# mapleCUx_large_210.net
KiCad netlist of a schematic drawn in EAGLE
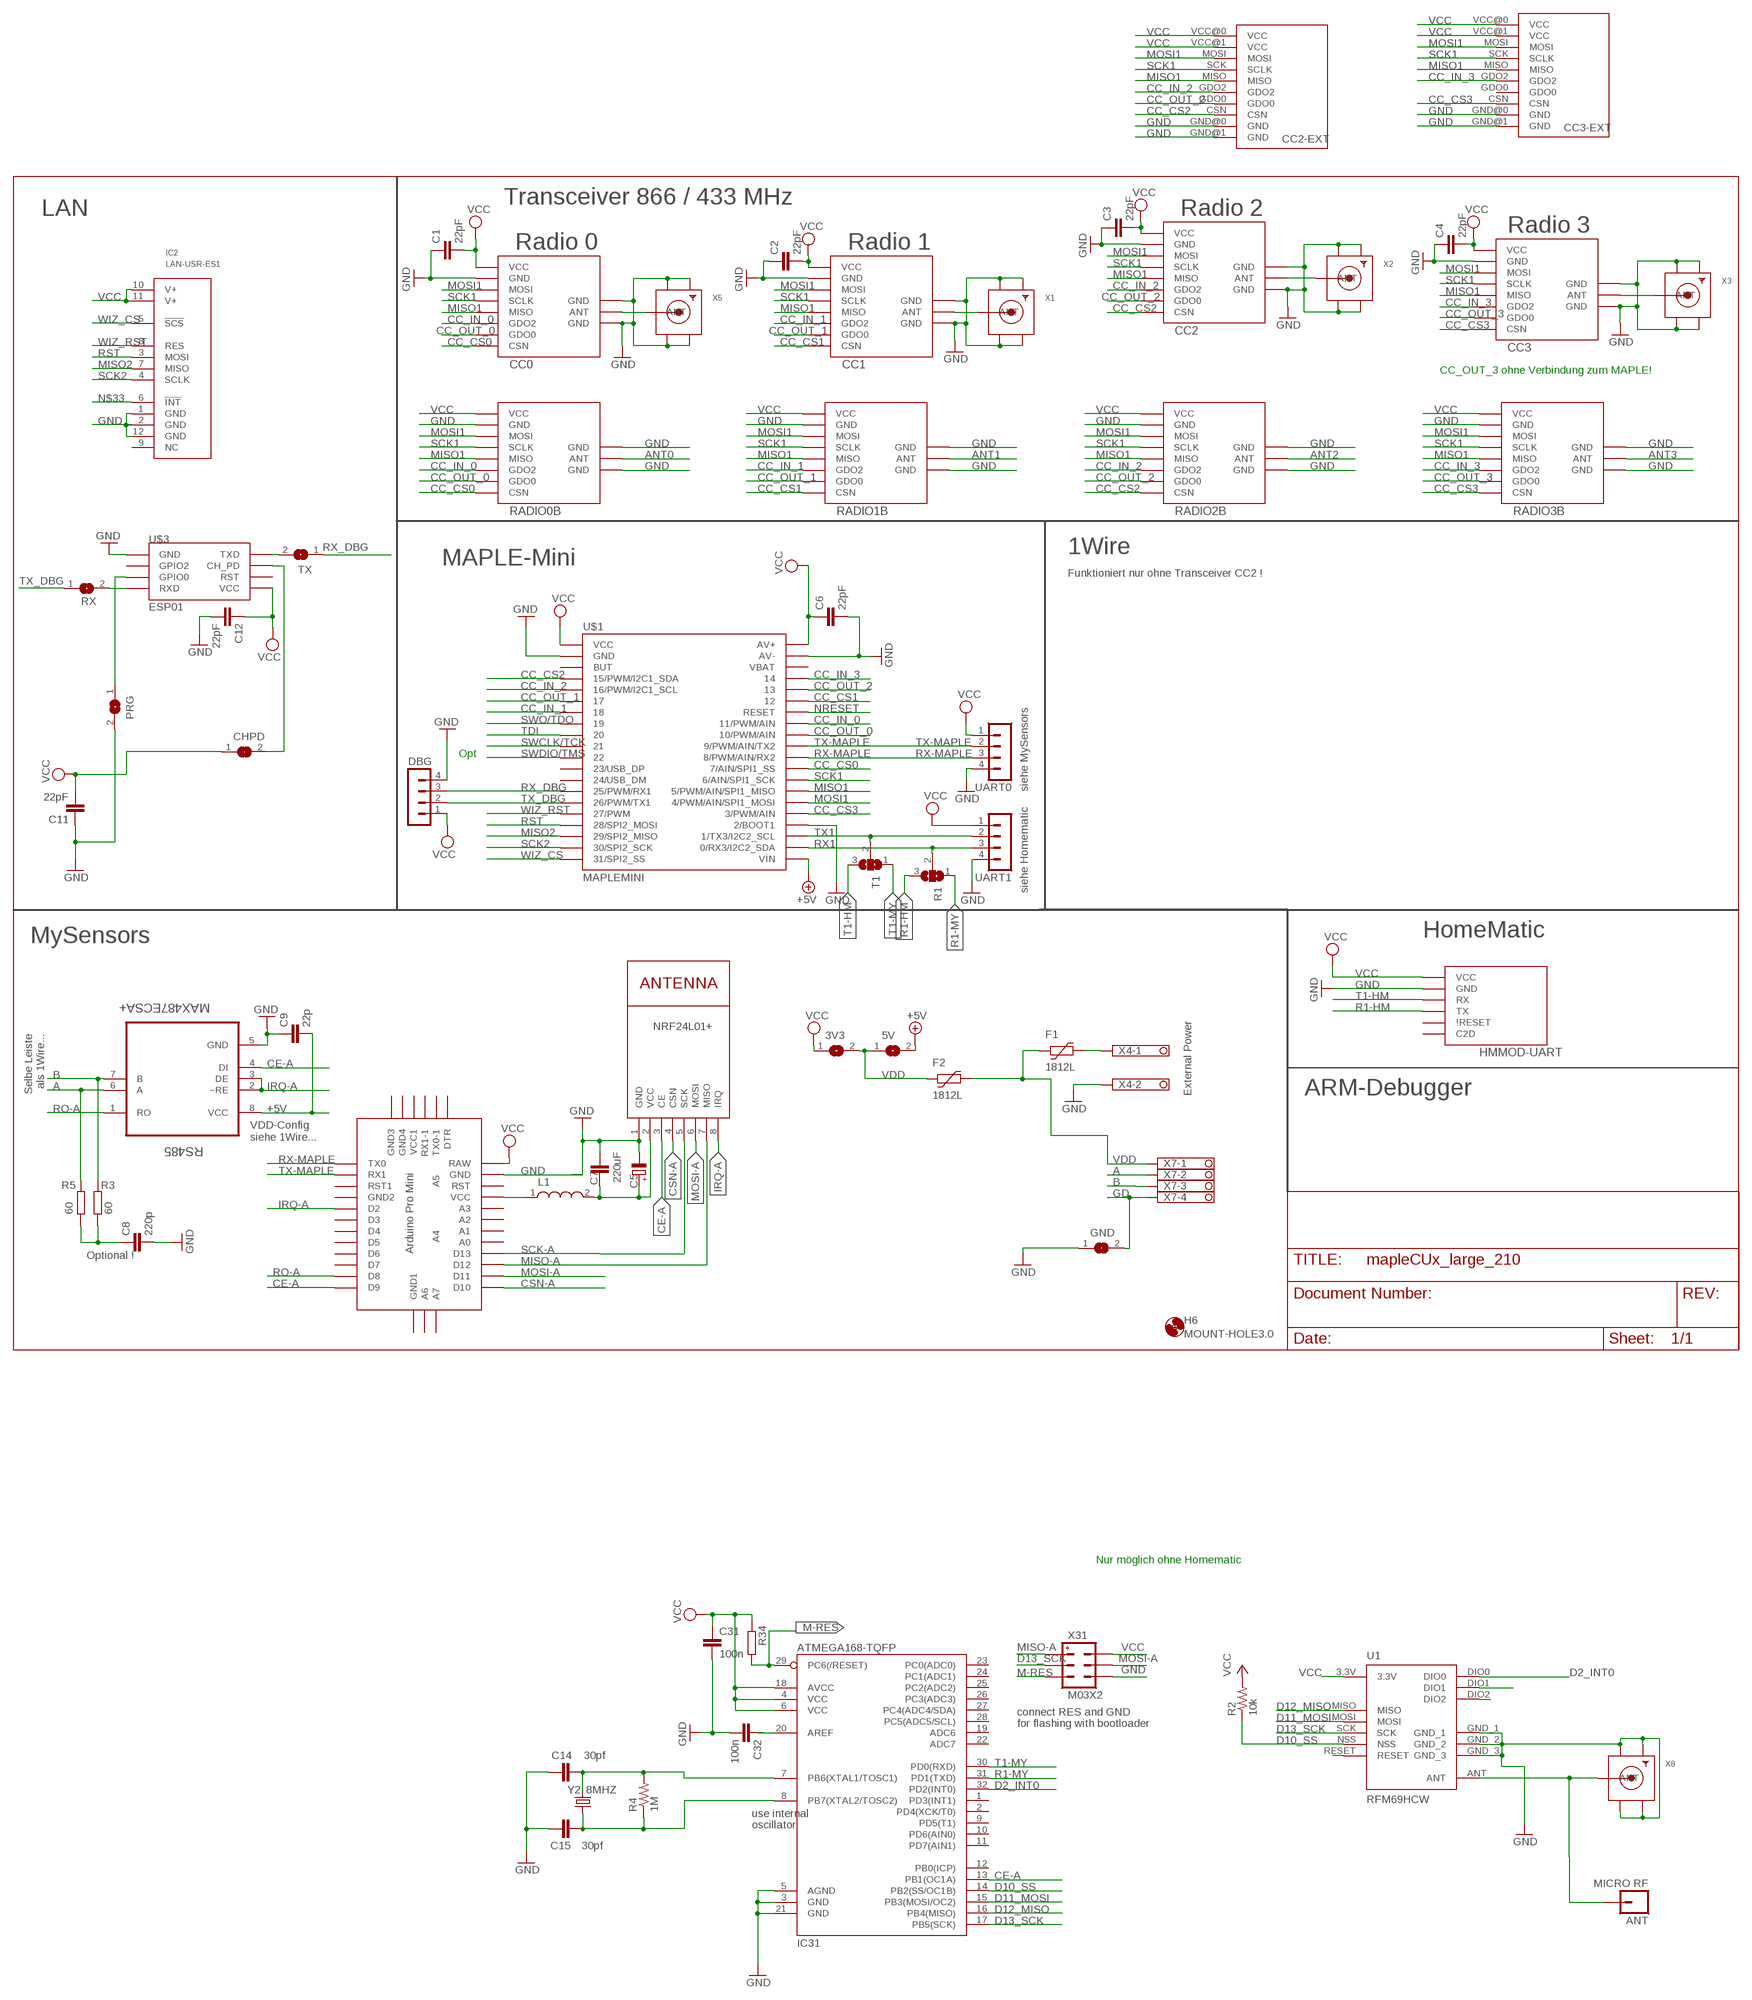
[diagram p0: schematic, sheet 1]

(export (version "E")
  (design (tool "Eeschema 10.0.6"))
  (components
    (comp (ref "3V3") (value "SJ") (footprint "eagle-import:SJ") (libsource (lib "eagle-import") (part "SJ")))
    (comp (ref "5V") (value "SJ") (footprint "eagle-import:SJ") (libsource (lib "eagle-import") (part "SJ")))
    (comp (ref "ANT")
      (value "MICRO RF")
      (footprint "eagle-import:1X01")
      (libsource (lib "eagle-import") (part "M01PTH"))
    )
    (comp (ref "C1")
      (value "22pF")
      (footprint "eagle-import:C0805")
      (libsource (lib "eagle-import") (part "C-EUC0805"))
    )
    (comp (ref "C2")
      (value "22pF")
      (footprint "eagle-import:C0805")
      (libsource (lib "eagle-import") (part "C-EUC0805"))
    )
    (comp (ref "C3")
      (value "22pF")
      (footprint "eagle-import:C0805")
      (libsource (lib "eagle-import") (part "C-EUC0805"))
    )
    (comp (ref "C4")
      (value "22pF")
      (footprint "eagle-import:C0805")
      (libsource (lib "eagle-import") (part "C-EUC0805"))
    )
    (comp (ref "C5")
      (value "220uF")
      (footprint "eagle-import:E5-8,5")
      (libsource (lib "eagle-import") (part "CPOL-EUE5-8.5"))
    )
    (comp (ref "C6")
      (value "22pF")
      (footprint "eagle-import:C0805")
      (libsource (lib "eagle-import") (part "C-EUC0805"))
    )
    (comp (ref "C7")
      (value "C-EUC1812")
      (footprint "eagle-import:C1812")
      (libsource (lib "eagle-import") (part "C-EUC1812"))
    )
    (comp (ref "C8")
      (value "220p")
      (footprint "eagle-import:C0805")
      (libsource (lib "eagle-import") (part "C-EUC0805"))
    )
    (comp (ref "C9")
      (value "22p")
      (footprint "eagle-import:C0805")
      (libsource (lib "eagle-import") (part "C-EUC0805"))
    )
    (comp (ref "C11")
      (value "22pF")
      (footprint "eagle-import:C0805")
      (libsource (lib "eagle-import") (part "C-EUC0805"))
    )
    (comp (ref "C12")
      (value "22pF")
      (footprint "eagle-import:C0805")
      (libsource (lib "eagle-import") (part "C-EUC0805"))
    )
    (comp (ref "C14")
      (value "30pf")
      (footprint "eagle-import:0805")
      (libsource (lib "eagle-import") (part "CAP0805"))
    )
    (comp (ref "C15")
      (value "30pf")
      (footprint "eagle-import:0805")
      (libsource (lib "eagle-import") (part "CAP0805"))
    )
    (comp (ref "C31")
      (value "100n")
      (footprint "eagle-import:C0805")
      (libsource (lib "eagle-import") (part "C-EUC0805"))
    )
    (comp (ref "C32")
      (value "100n")
      (footprint "eagle-import:C0805")
      (libsource (lib "eagle-import") (part "C-EUC0805"))
    )
    (comp (ref "CC0")
      (value "CC1101")
      (footprint "eagle-import:CC1101_MODULE1_SMD")
      (libsource (lib "eagle-import") (part "wireless_CC1101_MODULE1SMD"))
    )
    (comp (ref "CC1")
      (value "CC1101_MODULE1SMD")
      (footprint "eagle-import:CC1101_MODULE1_SMD")
      (libsource (lib "eagle-import") (part "wireless_CC1101_MODULE1SMD"))
    )
    (comp (ref "CC2")
      (value "CC1101_MODULE1SMD")
      (footprint "eagle-import:CC1101_MODULE1_SMD")
      (libsource (lib "eagle-import") (part "wireless_CC1101_MODULE1SMD"))
    )
    (comp (ref "CC2-EXT")
      (value "CC1101_MODULE3_DIL")
      (footprint "eagle-import:CC1101_MODULE3_DIL")
      (libsource (lib "eagle-import") (part "CC1101_MODULE3_DIL"))
    )
    (comp (ref "CC3")
      (value "CC1101_MODULE1SMD")
      (footprint "eagle-import:CC1101_MODULE1_SMD")
      (libsource (lib "eagle-import") (part "wireless_CC1101_MODULE1SMD"))
    )
    (comp (ref "CC3-EXT")
      (value "CC1101_MODULE3_DIL")
      (footprint "eagle-import:CC1101_MODULE3_DIL")
      (libsource (lib "eagle-import") (part "CC1101_MODULE3_DIL"))
    )
    (comp (ref "CHPD")
      (value "SJ")
      (footprint "eagle-import:SJ")
      (libsource (lib "eagle-import") (part "SJ"))
    )
    (comp (ref "DBG")
      (value "MA04-1")
      (footprint "eagle-import:MA04-1")
      (libsource (lib "eagle-import") (part "MA04-1"))
    )
    (comp (ref "F1")
      (value "1812L")
      (footprint "eagle-import:1812L")
      (libsource (lib "eagle-import") (part "1812L"))
    )
    (comp (ref "F2")
      (value "1812L")
      (footprint "eagle-import:1812L")
      (libsource (lib "eagle-import") (part "1812L"))
    )
    (comp (ref "GND") (value "SJ") (footprint "eagle-import:SJ") (libsource (lib "eagle-import") (part "SJ")))
    (comp (ref "H6")
      (value "MOUNT-HOLE3.0")
      (footprint "eagle-import:3,0")
      (libsource (lib "eagle-import") (part "MOUNT-HOLE3.0"))
    )
    (comp (ref "HMMOD-UART")
      (value "HM-MOD-UARTDIL")
      (footprint "eagle-import:HM-MOD-UART-DIL")
      (libsource (lib "eagle-import") (part "HM-MOD-UARTDIL"))
    )
    (comp (ref "IC2")
      (value "LAN-USR-ES1")
      (footprint "eagle-import:USR-ES1")
      (libsource (lib "eagle-import") (part "LAN-USR-ES1"))
    )
    (comp (ref "IC31")
      (value "ATMEGA168-TQFP")
      (footprint "eagle-import:TQFP32-08")
      (libsource (lib "eagle-import") (part "ATMEGA168-TQFP"))
    )
    (comp (ref "L1")
      (value "WE-KI_0805A")
      (footprint "eagle-import:WE-KI_0805A")
      (libsource (lib "eagle-import") (part "WE-KI_0805A"))
    )
    (comp (ref "NRF24L01+")
      (value "NRF24L01+")
      (footprint "eagle-import:WIRELESS-NRF24L01")
      (libsource (lib "eagle-import") (part "WIRELESS-NRF24L01"))
    )
    (comp (ref "PRG") (value "SJ") (footprint "eagle-import:SJ") (libsource (lib "eagle-import") (part "SJ")))
    (comp (ref "R1")
      (value "SJ2W")
      (footprint "eagle-import:SJ_2")
      (libsource (lib "eagle-import") (part "SJ2W"))
    )
    (comp (ref "R2")
      (value "10k")
      (footprint "eagle-import:0805")
      (libsource (lib "eagle-import") (part "RESISTOR0805-RES"))
    )
    (comp (ref "R3")
      (value "60")
      (footprint "eagle-import:R0805")
      (libsource (lib "eagle-import") (part "R-EU_R0805"))
    )
    (comp (ref "R4")
      (value "1M")
      (footprint "eagle-import:0805")
      (libsource (lib "eagle-import") (part "RESISTOR0805-RES"))
    )
    (comp (ref "R5")
      (value "60")
      (footprint "eagle-import:R0805")
      (libsource (lib "eagle-import") (part "R-EU_R0805"))
    )
    (comp (ref "R34")
      (value "R-EU_R0805")
      (footprint "eagle-import:R0805")
      (libsource (lib "eagle-import") (part "R-EU_R0805"))
    )
    (comp (ref "RADIO0B")
      (value "CC1101_MODULE1SMALL")
      (footprint "eagle-import:CC1101_MODULE1_SMD")
      (libsource (lib "eagle-import") (part "CC1101_MODULE1SMALL"))
    )
    (comp (ref "RADIO1B")
      (value "CC1101_MODULE1SMALL")
      (footprint "eagle-import:CC1101_MODULE1_SMD")
      (libsource (lib "eagle-import") (part "CC1101_MODULE1SMALL"))
    )
    (comp (ref "RADIO2B")
      (value "CC1101_MODULE1SMALL")
      (footprint "eagle-import:CC1101_MODULE1_SMD")
      (libsource (lib "eagle-import") (part "CC1101_MODULE1SMALL"))
    )
    (comp (ref "RADIO3B")
      (value "CC1101_MODULE1SMALL")
      (footprint "eagle-import:CC1101_MODULE1_SMD")
      (libsource (lib "eagle-import") (part "CC1101_MODULE1SMALL"))
    )
    (comp (ref "RS485")
      (value "MAX487ECSA+")
      (footprint "eagle-import:SOIC127P600X175-8N")
      (libsource (lib "eagle-import") (part "MAX487ECSA+"))
    )
    (comp (ref "RX") (value "SJ") (footprint "eagle-import:SJ") (libsource (lib "eagle-import") (part "SJ")))
    (comp (ref "T1")
      (value "SJ2W")
      (footprint "eagle-import:SJ_2")
      (libsource (lib "eagle-import") (part "SJ2W"))
    )
    (comp (ref "TX") (value "SJ") (footprint "eagle-import:SJ") (libsource (lib "eagle-import") (part "SJ")))
    (comp (ref "U$1")
      (value "MAPLEMINI")
      (footprint "eagle-import:20-DIP")
      (libsource (lib "eagle-import") (part "MAPLEMINI"))
    )
    (comp (ref "U$2")
      (value "ABK-PRO-MINI")
      (footprint "eagle-import:ABK-PRO-MINI")
      (libsource (lib "eagle-import") (part "ABK-PRO-MINI"))
    )
    (comp (ref "U$3")
      (value "ESP01")
      (footprint "eagle-import:ESP01")
      (libsource (lib "eagle-import") (part "ESP01"))
    )
    (comp (ref "U1")
      (value "RFM69HCW")
      (footprint "eagle-import:RFM69HCW-XXXS2")
      (libsource (lib "eagle-import") (part "RFM69HCW"))
    )
    (comp (ref "UART0")
      (value "MA04-1")
      (footprint "eagle-import:MA04-1")
      (libsource (lib "eagle-import") (part "MA04-1"))
    )
    (comp (ref "UART1")
      (value "MA04-1")
      (footprint "eagle-import:MA04-1")
      (libsource (lib "eagle-import") (part "MA04-1"))
    )
    (comp (ref "X1")
      (value "SMACONNECTOR_EDGE")
      (footprint "eagle-import:SMA_EDGELAUNCH")
      (libsource (lib "eagle-import") (part "SMACONNECTOR_EDGE"))
    )
    (comp (ref "X2")
      (value "SMACONNECTOR_EDGE")
      (footprint "eagle-import:SMA_EDGELAUNCH")
      (libsource (lib "eagle-import") (part "SMACONNECTOR_EDGE"))
    )
    (comp (ref "X3")
      (value "SMACONNECTOR_EDGE")
      (footprint "eagle-import:SMA_EDGELAUNCH")
      (libsource (lib "eagle-import") (part "SMACONNECTOR_EDGE"))
    )
    (comp (ref "X4")
      (value "1751248")
      (footprint "eagle-import:1751248")
      (libsource (lib "eagle-import") (part "1751248"))
    )
    (comp (ref "X5")
      (value "SMACONNECTOR_EDGE")
      (footprint "eagle-import:SMA_EDGELAUNCH")
      (libsource (lib "eagle-import") (part "SMACONNECTOR_EDGE"))
    )
    (comp (ref "X7")
      (value "1751264")
      (footprint "eagle-import:1751264")
      (libsource (lib "eagle-import") (part "1751264"))
    )
    (comp (ref "X8")
      (value "SMACONNECTOR_EDGE_UFL")
      (footprint "eagle-import:SMA_EDGELAUNCH_UFL")
      (libsource (lib "eagle-import") (part "SMACONNECTOR_EDGE_UFL"))
    )
    (comp (ref "X31")
      (value "M03X2")
      (footprint "eagle-import:2X03-1.27MM_SMD")
      (libsource (lib "eagle-import") (part "M03X2"))
    )
    (comp (ref "Y2")
      (value "8MHZ")
      (footprint "eagle-import:CRYSTAL-TXC-7A")
      (libsource (lib "eagle-import") (part "CRYSTALTXC-7A"))
    )
  )
  (nets
    (net (code "1") (name "+5V") (class "Default")
      (node (ref "5V") (pin "2") (pinfunction "2_2") (pintype "passive"))
      (node (ref "C9") (pin "2") (pinfunction "2_2") (pintype "passive"))
      (node (ref "RS485") (pin "8") (pinfunction "VCC_8") (pintype "power_in"))
      (node (ref "U$1") (pin "21") (pinfunction "VIN_21") (pintype "bidirectional"))
    )
    (net (code "2") (name "/A") (class "Default")
      (node (ref "R5") (pin "2") (pinfunction "2_2") (pintype "passive"))
      (node (ref "RS485") (pin "6") (pinfunction "A_6") (pintype "bidirectional"))
      (node (ref "X7") (pin "2") (pinfunction "K_2") (pintype "passive"))
    )
    (net (code "3") (name "/ANT0") (class "Default")
      (node (ref "CC0") (pin "ANT") (pinfunction "ANT_ANT") (pintype "output"))
      (node (ref "RADIO0B") (pin "ANT") (pinfunction "ANT_ANT") (pintype "output"))
      (node (ref "X5") (pin "P") (pinfunction "ANT_P") (pintype "bidirectional"))
    )
    (net (code "4") (name "/ANT1") (class "Default")
      (node (ref "CC1") (pin "ANT") (pinfunction "ANT_ANT") (pintype "output"))
      (node (ref "RADIO1B") (pin "ANT") (pinfunction "ANT_ANT") (pintype "output"))
      (node (ref "X1") (pin "P") (pinfunction "ANT_P") (pintype "bidirectional"))
    )
    (net (code "5") (name "/ANT2") (class "Default")
      (node (ref "CC2") (pin "ANT") (pinfunction "ANT_ANT") (pintype "output"))
      (node (ref "RADIO2B") (pin "ANT") (pinfunction "ANT_ANT") (pintype "output"))
      (node (ref "X2") (pin "P") (pinfunction "ANT_P") (pintype "bidirectional"))
    )
    (net (code "6") (name "/ANT3") (class "Default")
      (node (ref "CC3") (pin "ANT") (pinfunction "ANT_ANT") (pintype "output"))
      (node (ref "RADIO3B") (pin "ANT") (pinfunction "ANT_ANT") (pintype "output"))
      (node (ref "X3") (pin "P") (pinfunction "ANT_P") (pintype "bidirectional"))
    )
    (net (code "7") (name "/B") (class "Default")
      (node (ref "R3") (pin "2") (pinfunction "2_2") (pintype "passive"))
      (node (ref "RS485") (pin "7") (pinfunction "B_7") (pintype "bidirectional"))
      (node (ref "X7") (pin "3") (pinfunction "K_3") (pintype "passive"))
    )
    (net (code "8") (name "/CC_CS0") (class "Default")
      (node (ref "CC0") (pin "CSN") (pinfunction "CSN_CSN") (pintype "bidirectional"))
      (node (ref "RADIO0B") (pin "CSN") (pinfunction "CSN_CSN") (pintype "bidirectional"))
      (node (ref "U$1") (pin "29") (pinfunction "7/AIN/SPI1_SS_29") (pintype "bidirectional"))
    )
    (net (code "9") (name "/CC_CS1") (class "Default")
      (node (ref "CC1") (pin "CSN") (pinfunction "CSN_CSN") (pintype "bidirectional"))
      (node (ref "RADIO1B") (pin "CSN") (pinfunction "CSN_CSN") (pintype "bidirectional"))
      (node (ref "U$1") (pin "35") (pinfunction "12_35") (pintype "bidirectional"))
    )
    (net (code "10") (name "/CC_CS2") (class "Default")
      (node (ref "CC2") (pin "CSN") (pinfunction "CSN_CSN") (pintype "bidirectional"))
      (node (ref "CC2-EXT") (pin "CSN") (pinfunction "CSN_CSN") (pintype "bidirectional"))
      (node (ref "RADIO2B") (pin "CSN") (pinfunction "CSN_CSN") (pintype "bidirectional"))
      (node (ref "U$1") (pin "4") (pinfunction "15/PWM/I2C1_SDA_4") (pintype "bidirectional"))
    )
    (net (code "11") (name "/CC_CS3") (class "Default")
      (node (ref "CC3") (pin "CSN") (pinfunction "CSN_CSN") (pintype "bidirectional"))
      (node (ref "CC3-EXT") (pin "CSN") (pinfunction "CSN_CSN") (pintype "bidirectional"))
      (node (ref "RADIO3B") (pin "CSN") (pinfunction "CSN_CSN") (pintype "bidirectional"))
      (node (ref "U$1") (pin "25") (pinfunction "3/PWM/AIN_25") (pintype "bidirectional"))
    )
    (net (code "12") (name "/CC_IN_0") (class "Default")
      (node (ref "CC0") (pin "GDO2") (pinfunction "GDO2_GDO2") (pintype "bidirectional"))
      (node (ref "RADIO0B") (pin "GDO2") (pinfunction "GDO2_GDO2") (pintype "bidirectional"))
      (node (ref "U$1") (pin "33") (pinfunction "11/PWM/AIN_33") (pintype "bidirectional"))
    )
    (net (code "13") (name "/CC_IN_1") (class "Default")
      (node (ref "CC1") (pin "GDO2") (pinfunction "GDO2_GDO2") (pintype "bidirectional"))
      (node (ref "RADIO1B") (pin "GDO2") (pinfunction "GDO2_GDO2") (pintype "bidirectional"))
      (node (ref "U$1") (pin "7") (pinfunction "18_7") (pintype "bidirectional"))
    )
    (net (code "14") (name "/CC_IN_2") (class "Default")
      (node (ref "CC2") (pin "GDO2") (pinfunction "GDO2_GDO2") (pintype "bidirectional"))
      (node (ref "CC2-EXT") (pin "GDO2") (pinfunction "GDO2_GDO2") (pintype "bidirectional"))
      (node (ref "RADIO2B") (pin "GDO2") (pinfunction "GDO2_GDO2") (pintype "bidirectional"))
      (node (ref "U$1") (pin "5") (pinfunction "16/PWM/I2C1_SCL_5") (pintype "bidirectional"))
    )
    (net (code "15") (name "/CC_IN_3") (class "Default")
      (node (ref "CC3") (pin "GDO2") (pinfunction "GDO2_GDO2") (pintype "bidirectional"))
      (node (ref "CC3-EXT") (pin "GDO2") (pinfunction "GDO2_GDO2") (pintype "bidirectional"))
      (node (ref "RADIO3B") (pin "GDO2") (pinfunction "GDO2_GDO2") (pintype "bidirectional"))
      (node (ref "U$1") (pin "37") (pinfunction "14_37") (pintype "bidirectional"))
    )
    (net (code "16") (name "/CC_OUT_0") (class "Default")
      (node (ref "CC0") (pin "GDO0") (pinfunction "GDO0_GDO0") (pintype "bidirectional"))
      (node (ref "RADIO0B") (pin "GDO0") (pinfunction "GDO0_GDO0") (pintype "bidirectional"))
      (node (ref "U$1") (pin "32") (pinfunction "10/PWM/AIN_32") (pintype "bidirectional"))
    )
    (net (code "17") (name "/CC_OUT_1") (class "Default")
      (node (ref "CC1") (pin "GDO0") (pinfunction "GDO0_GDO0") (pintype "bidirectional"))
      (node (ref "RADIO1B") (pin "GDO0") (pinfunction "GDO0_GDO0") (pintype "bidirectional"))
      (node (ref "U$1") (pin "6") (pinfunction "17_6") (pintype "bidirectional"))
    )
    (net (code "18") (name "/CC_OUT_2") (class "Default")
      (node (ref "CC2") (pin "GDO0") (pinfunction "GDO0_GDO0") (pintype "bidirectional"))
      (node (ref "CC2-EXT") (pin "GDO0") (pinfunction "GDO0_GDO0") (pintype "bidirectional"))
      (node (ref "RADIO2B") (pin "GDO0") (pinfunction "GDO0_GDO0") (pintype "bidirectional"))
      (node (ref "U$1") (pin "36") (pinfunction "13_36") (pintype "bidirectional"))
    )
    (net (code "19") (name "/CC_OUT_3") (class "Default")
      (node (ref "CC3") (pin "GDO0") (pinfunction "GDO0_GDO0") (pintype "bidirectional"))
      (node (ref "RADIO3B") (pin "GDO0") (pinfunction "GDO0_GDO0") (pintype "bidirectional"))
    )
    (net (code "20") (name "/D2_INT0") (class "Default")
      (node (ref "IC31") (pin "32") (pinfunction "PD2(INT0)_32") (pintype "bidirectional"))
      (node (ref "U1") (pin "DIO0") (pinfunction "DIO0_DIO0") (pintype "bidirectional"))
    )
    (net (code "21") (name "/D10_SS") (class "Default")
      (node (ref "IC31") (pin "14") (pinfunction "PB2(SS/OC1B)_14") (pintype "bidirectional"))
      (node (ref "R2") (pin "1") (pinfunction "1_1") (pintype "passive"))
      (node (ref "U1") (pin "NSS") (pinfunction "NSS_NSS") (pintype "input"))
    )
    (net (code "22") (name "/D11_MOSI") (class "Default")
      (node (ref "IC31") (pin "15") (pinfunction "PB3(MOSI/OC2)_15") (pintype "bidirectional"))
      (node (ref "U1") (pin "MOSI") (pinfunction "MOSI_MOSI") (pintype "input"))
    )
    (net (code "23") (name "/D12_MISO") (class "Default")
      (node (ref "IC31") (pin "16") (pinfunction "PB4(MISO)_16") (pintype "bidirectional"))
      (node (ref "U1") (pin "MISO") (pinfunction "MISO_MISO") (pintype "bidirectional"))
    )
    (net (code "24") (name "/D13_SCK") (class "Default")
      (node (ref "IC31") (pin "17") (pinfunction "PB5(SCK)_17") (pintype "bidirectional"))
      (node (ref "U1") (pin "SCK") (pinfunction "SCK_SCK") (pintype "input"))
      (node (ref "X31") (pin "P$3") (pinfunction "3_P$3") (pintype "passive"))
    )
    (net (code "25") (name "/GD") (class "Default")
      (node (ref "GND") (pin "2") (pinfunction "2_2") (pintype "passive"))
      (node (ref "X7") (pin "4") (pinfunction "K_4") (pintype "passive"))
    )
    (net (code "26") (name "/M-RES") (class "Default")
      (node (ref "IC31") (pin "29") (pinfunction "PC6(/RESET)_29") (pintype "bidirectional"))
      (node (ref "R34") (pin "2") (pinfunction "2_2") (pintype "passive"))
      (node (ref "X31") (pin "P$5") (pinfunction "5_P$5") (pintype "passive"))
    )
    (net (code "27") (name "/MISO-A") (class "Default")
      (node (ref "NRF24L01+") (pin "7") (pinfunction "MISO_7") (pintype "bidirectional"))
      (node (ref "U$2") (pin "D12") (pinfunction "D12_D12") (pintype "bidirectional"))
      (node (ref "X31") (pin "P$1") (pinfunction "1_P$1") (pintype "passive"))
    )
    (net (code "28") (name "/MISO1") (class "Default")
      (node (ref "CC0") (pin "MISO") (pinfunction "MISO_MISO") (pintype "bidirectional"))
      (node (ref "CC1") (pin "MISO") (pinfunction "MISO_MISO") (pintype "bidirectional"))
      (node (ref "CC2") (pin "MISO") (pinfunction "MISO_MISO") (pintype "bidirectional"))
      (node (ref "CC2-EXT") (pin "MISO") (pinfunction "MISO_MISO") (pintype "bidirectional"))
      (node (ref "CC3") (pin "MISO") (pinfunction "MISO_MISO") (pintype "bidirectional"))
      (node (ref "CC3-EXT") (pin "MISO") (pinfunction "MISO_MISO") (pintype "bidirectional"))
      (node (ref "RADIO0B") (pin "MISO") (pinfunction "MISO_MISO") (pintype "bidirectional"))
      (node (ref "RADIO1B") (pin "MISO") (pinfunction "MISO_MISO") (pintype "bidirectional"))
      (node (ref "RADIO2B") (pin "MISO") (pinfunction "MISO_MISO") (pintype "bidirectional"))
      (node (ref "RADIO3B") (pin "MISO") (pinfunction "MISO_MISO") (pintype "bidirectional"))
      (node (ref "U$1") (pin "27") (pinfunction "5/PWM/AIN/SPI1_MISO_27") (pintype "bidirectional"))
    )
    (net (code "29") (name "/MISO2") (class "Default")
      (node (ref "IC2") (pin "7") (pinfunction "MISO_7") (pintype "bidirectional"))
      (node (ref "U$1") (pin "18") (pinfunction "29/SPI2_MISO_18") (pintype "bidirectional"))
    )
    (net (code "30") (name "/MOSI1") (class "Default")
      (node (ref "CC0") (pin "MOSI") (pinfunction "MOSI_MOSI") (pintype "bidirectional"))
      (node (ref "CC1") (pin "MOSI") (pinfunction "MOSI_MOSI") (pintype "bidirectional"))
      (node (ref "CC2") (pin "MOSI") (pinfunction "MOSI_MOSI") (pintype "bidirectional"))
      (node (ref "CC2-EXT") (pin "MOSI") (pinfunction "MOSI_MOSI") (pintype "bidirectional"))
      (node (ref "CC3") (pin "MOSI") (pinfunction "MOSI_MOSI") (pintype "bidirectional"))
      (node (ref "CC3-EXT") (pin "MOSI") (pinfunction "MOSI_MOSI") (pintype "bidirectional"))
      (node (ref "RADIO0B") (pin "MOSI") (pinfunction "MOSI_MOSI") (pintype "bidirectional"))
      (node (ref "RADIO1B") (pin "MOSI") (pinfunction "MOSI_MOSI") (pintype "bidirectional"))
      (node (ref "RADIO2B") (pin "MOSI") (pinfunction "MOSI_MOSI") (pintype "bidirectional"))
      (node (ref "RADIO3B") (pin "MOSI") (pinfunction "MOSI_MOSI") (pintype "bidirectional"))
      (node (ref "U$1") (pin "26") (pinfunction "4/PWM/AIN/SPI1_MOSI_26") (pintype "bidirectional"))
    )
    (net (code "31") (name "/N$33") (class "Default")
      (node (ref "IC2") (pin "6") (pinfunction "~{INT}_6") (pintype "output"))
    )
    (net (code "32") (name "/NRESET") (class "Default")
      (node (ref "U$1") (pin "34") (pinfunction "RESET_34") (pintype "bidirectional"))
    )
    (net (code "33") (name "/RO-A") (class "Default")
      (node (ref "RS485") (pin "1") (pinfunction "RO_1") (pintype "output"))
      (node (ref "U$2") (pin "D8") (pinfunction "D8_D8") (pintype "bidirectional"))
    )
    (net (code "34") (name "/RST") (class "Default")
      (node (ref "IC2") (pin "3") (pinfunction "MOSI_3") (pintype "bidirectional"))
      (node (ref "U$1") (pin "17") (pinfunction "28/SPI2_MOSI_17") (pintype "bidirectional"))
    )
    (net (code "35") (name "/RX-MAPLE") (class "Default")
      (node (ref "U$1") (pin "30") (pinfunction "8/PWM/AIN/RX2_30") (pintype "bidirectional"))
      (node (ref "U$2") (pin "TX0") (pinfunction "TX0_TX0") (pintype "bidirectional"))
      (node (ref "UART0") (pin "3") (pinfunction "3_3") (pintype "passive"))
    )
    (net (code "36") (name "/RX1") (class "Default")
      (node (ref "R1") (pin "2") (pinfunction "2_2") (pintype "passive"))
      (node (ref "U$1") (pin "22") (pinfunction "0/RX3/I2C2_SDA_22") (pintype "bidirectional"))
      (node (ref "UART1") (pin "3") (pinfunction "3_3") (pintype "passive"))
    )
    (net (code "37") (name "/RX_DBG") (class "Default")
      (node (ref "DBG") (pin "3") (pinfunction "3_3") (pintype "passive"))
      (node (ref "TX") (pin "1") (pinfunction "1_1") (pintype "passive"))
      (node (ref "U$1") (pin "14") (pinfunction "25/PWM/RX1_14") (pintype "bidirectional"))
    )
    (net (code "38") (name "/SCK-A") (class "Default")
      (node (ref "NRF24L01+") (pin "5") (pinfunction "SCK_5") (pintype "bidirectional"))
      (node (ref "U$2") (pin "D13") (pinfunction "D13_D13") (pintype "bidirectional"))
    )
    (net (code "39") (name "/SCK1") (class "Default")
      (node (ref "CC0") (pin "SCLK") (pinfunction "SCLK_SCLK") (pintype "bidirectional"))
      (node (ref "CC1") (pin "SCLK") (pinfunction "SCLK_SCLK") (pintype "bidirectional"))
      (node (ref "CC2") (pin "SCLK") (pinfunction "SCLK_SCLK") (pintype "bidirectional"))
      (node (ref "CC2-EXT") (pin "SCK") (pinfunction "SCLK_SCK") (pintype "bidirectional"))
      (node (ref "CC3") (pin "SCLK") (pinfunction "SCLK_SCLK") (pintype "bidirectional"))
      (node (ref "CC3-EXT") (pin "SCK") (pinfunction "SCLK_SCK") (pintype "bidirectional"))
      (node (ref "RADIO0B") (pin "SCLK") (pinfunction "SCLK_SCLK") (pintype "bidirectional"))
      (node (ref "RADIO1B") (pin "SCLK") (pinfunction "SCLK_SCLK") (pintype "bidirectional"))
      (node (ref "RADIO2B") (pin "SCLK") (pinfunction "SCLK_SCLK") (pintype "bidirectional"))
      (node (ref "RADIO3B") (pin "SCLK") (pinfunction "SCLK_SCLK") (pintype "bidirectional"))
      (node (ref "U$1") (pin "28") (pinfunction "6/AIN/SPI1_SCK_28") (pintype "bidirectional"))
    )
    (net (code "40") (name "/SCK2") (class "Default")
      (node (ref "IC2") (pin "4") (pinfunction "SCLK_4") (pintype "input"))
      (node (ref "U$1") (pin "19") (pinfunction "30/SPI2_SCK_19") (pintype "bidirectional"))
    )
    (net (code "41") (name "/SWCLK{slash}TCK") (class "Default")
      (node (ref "U$1") (pin "10") (pinfunction "21_10") (pintype "bidirectional"))
    )
    (net (code "42") (name "/SWDIO{slash}TMS") (class "Default")
      (node (ref "U$1") (pin "11") (pinfunction "22_11") (pintype "bidirectional"))
    )
    (net (code "43") (name "/SWO{slash}TDO") (class "Default")
      (node (ref "U$1") (pin "8") (pinfunction "19_8") (pintype "bidirectional"))
    )
    (net (code "44") (name "/TDI") (class "Default")
      (node (ref "U$1") (pin "9") (pinfunction "20_9") (pintype "bidirectional"))
    )
    (net (code "45") (name "/TX-MAPLE") (class "Default")
      (node (ref "U$1") (pin "31") (pinfunction "9/PWM/AIN/TX2_31") (pintype "bidirectional"))
      (node (ref "U$2") (pin "RX1") (pinfunction "RX1_RX1") (pintype "bidirectional"))
      (node (ref "UART0") (pin "2") (pinfunction "2_2") (pintype "passive"))
    )
    (net (code "46") (name "/TX1") (class "Default")
      (node (ref "T1") (pin "2") (pinfunction "2_2") (pintype "passive"))
      (node (ref "U$1") (pin "23") (pinfunction "1/TX3/I2C2_SCL_23") (pintype "bidirectional"))
      (node (ref "UART1") (pin "2") (pinfunction "2_2") (pintype "passive"))
    )
    (net (code "47") (name "/TX_DBG") (class "Default")
      (node (ref "DBG") (pin "2") (pinfunction "2_2") (pintype "passive"))
      (node (ref "RX") (pin "1") (pinfunction "1_1") (pintype "passive"))
      (node (ref "U$1") (pin "15") (pinfunction "26/PWM/TX1_15") (pintype "bidirectional"))
    )
    (net (code "48") (name "/VDD") (class "Default")
      (node (ref "3V3") (pin "2") (pinfunction "2_2") (pintype "passive"))
      (node (ref "5V") (pin "1") (pinfunction "1_1") (pintype "passive"))
      (node (ref "F1") (pin "P$1") (pinfunction "1_P$1") (pintype "passive"))
      (node (ref "F2") (pin "P$1") (pinfunction "1_P$1") (pintype "passive"))
      (node (ref "F2") (pin "P$2") (pinfunction "2_P$2") (pintype "passive"))
      (node (ref "X7") (pin "1") (pinfunction "K_1") (pintype "passive"))
    )
    (net (code "49") (name "/WIZ_CS") (class "Default")
      (node (ref "IC2") (pin "5") (pinfunction "~{SCS}_5") (pintype "input"))
      (node (ref "U$1") (pin "20") (pinfunction "31/SPI2_SS_20") (pintype "bidirectional"))
    )
    (net (code "50") (name "/WIZ_RST") (class "Default")
      (node (ref "IC2") (pin "8") (pinfunction "RES_8") (pintype "input"))
      (node (ref "U$1") (pin "16") (pinfunction "27/PWM_16") (pintype "bidirectional"))
    )
    (net (code "51") (name "CE-A") (class "Default")
      (node (ref "IC31") (pin "13") (pinfunction "PB1(OC1A)_13") (pintype "bidirectional"))
      (node (ref "NRF24L01+") (pin "3") (pinfunction "CE_3") (pintype "bidirectional"))
      (node (ref "RS485") (pin "4") (pinfunction "DI_4") (pintype "input"))
      (node (ref "U$2") (pin "D9") (pinfunction "D9_D9") (pintype "bidirectional"))
    )
    (net (code "52") (name "CSN-A") (class "Default")
      (node (ref "NRF24L01+") (pin "4") (pinfunction "CSN_4") (pintype "bidirectional"))
      (node (ref "U$2") (pin "D10") (pinfunction "D10_D10") (pintype "bidirectional"))
    )
    (net (code "53") (name "GND") (class "Default")
      (node (ref "C1") (pin "1") (pinfunction "1_1") (pintype "passive"))
      (node (ref "C11") (pin "1") (pinfunction "1_1") (pintype "passive"))
      (node (ref "C12") (pin "2") (pinfunction "2_2") (pintype "passive"))
      (node (ref "C14") (pin "1") (pinfunction "1_1") (pintype "passive"))
      (node (ref "C15") (pin "1") (pinfunction "1_1") (pintype "passive"))
      (node (ref "C2") (pin "1") (pinfunction "1_1") (pintype "passive"))
      (node (ref "C3") (pin "1") (pinfunction "1_1") (pintype "passive"))
      (node (ref "C31") (pin "2") (pinfunction "2_2") (pintype "passive"))
      (node (ref "C32") (pin "2") (pinfunction "2_2") (pintype "passive"))
      (node (ref "C4") (pin "1") (pinfunction "1_1") (pintype "passive"))
      (node (ref "C5") (pin "-") (pinfunction "-_-") (pintype "passive"))
      (node (ref "C6") (pin "2") (pinfunction "2_2") (pintype "passive"))
      (node (ref "C7") (pin "1") (pinfunction "1_1") (pintype "passive"))
      (node (ref "C8") (pin "2") (pinfunction "2_2") (pintype "passive"))
      (node (ref "C9") (pin "1") (pinfunction "1_1") (pintype "passive"))
      (node (ref "CC0") (pin "GND@0") (pinfunction "GND_GND@0") (pintype "power_in"))
      (node (ref "CC0") (pin "GND@1") (pinfunction "GND_GND@1") (pintype "power_in"))
      (node (ref "CC0") (pin "GND@2") (pinfunction "GND_GND@2") (pintype "power_in"))
      (node (ref "CC1") (pin "GND@0") (pinfunction "GND_GND@0") (pintype "power_in"))
      (node (ref "CC1") (pin "GND@1") (pinfunction "GND_GND@1") (pintype "power_in"))
      (node (ref "CC1") (pin "GND@2") (pinfunction "GND_GND@2") (pintype "power_in"))
      (node (ref "CC2") (pin "GND@0") (pinfunction "GND_GND@0") (pintype "power_in"))
      (node (ref "CC2") (pin "GND@1") (pinfunction "GND_GND@1") (pintype "power_in"))
      (node (ref "CC2") (pin "GND@2") (pinfunction "GND_GND@2") (pintype "power_in"))
      (node (ref "CC2-EXT") (pin "GND@0") (pinfunction "GND_GND@0") (pintype "power_in"))
      (node (ref "CC2-EXT") (pin "GND@1") (pinfunction "GND_GND@1") (pintype "power_in"))
      (node (ref "CC3") (pin "GND@0") (pinfunction "GND_GND@0") (pintype "power_in"))
      (node (ref "CC3") (pin "GND@1") (pinfunction "GND_GND@1") (pintype "power_in"))
      (node (ref "CC3") (pin "GND@2") (pinfunction "GND_GND@2") (pintype "power_in"))
      (node (ref "CC3-EXT") (pin "GND@0") (pinfunction "GND_GND@0") (pintype "power_in"))
      (node (ref "CC3-EXT") (pin "GND@1") (pinfunction "GND_GND@1") (pintype "power_in"))
      (node (ref "DBG") (pin "4") (pinfunction "4_4") (pintype "passive"))
      (node (ref "GND") (pin "1") (pinfunction "1_1") (pintype "passive"))
      (node (ref "HMMOD-UART") (pin "2") (pinfunction "GND_2") (pintype "power_in"))
      (node (ref "IC2") (pin "1") (pinfunction "GND_1") (pintype "power_in"))
      (node (ref "IC2") (pin "12") (pinfunction "GND_12") (pintype "power_in"))
      (node (ref "IC2") (pin "2") (pinfunction "GND_2") (pintype "power_in"))
      (node (ref "IC31") (pin "21") (pinfunction "GND_21") (pintype "bidirectional"))
      (node (ref "IC31") (pin "3") (pinfunction "GND_3") (pintype "bidirectional"))
      (node (ref "IC31") (pin "5") (pinfunction "AGND_5") (pintype "bidirectional"))
      (node (ref "NRF24L01+") (pin "1") (pinfunction "GND_1") (pintype "power_in"))
      (node (ref "PRG") (pin "2") (pinfunction "2_2") (pintype "passive"))
      (node (ref "RADIO0B") (pin "GND@0") (pinfunction "GND_GND@0") (pintype "power_in"))
      (node (ref "RADIO0B") (pin "GND@1") (pinfunction "GND_GND@1") (pintype "power_in"))
      (node (ref "RADIO0B") (pin "GND@2") (pinfunction "GND_GND@2") (pintype "power_in"))
      (node (ref "RADIO1B") (pin "GND@0") (pinfunction "GND_GND@0") (pintype "power_in"))
      (node (ref "RADIO1B") (pin "GND@1") (pinfunction "GND_GND@1") (pintype "power_in"))
      (node (ref "RADIO1B") (pin "GND@2") (pinfunction "GND_GND@2") (pintype "power_in"))
      (node (ref "RADIO2B") (pin "GND@0") (pinfunction "GND_GND@0") (pintype "power_in"))
      (node (ref "RADIO2B") (pin "GND@1") (pinfunction "GND_GND@1") (pintype "power_in"))
      (node (ref "RADIO2B") (pin "GND@2") (pinfunction "GND_GND@2") (pintype "power_in"))
      (node (ref "RADIO3B") (pin "GND@0") (pinfunction "GND_GND@0") (pintype "power_in"))
      (node (ref "RADIO3B") (pin "GND@1") (pinfunction "GND_GND@1") (pintype "power_in"))
      (node (ref "RADIO3B") (pin "GND@2") (pinfunction "GND_GND@2") (pintype "power_in"))
      (node (ref "RS485") (pin "5") (pinfunction "GND_5") (pintype "passive"))
      (node (ref "U$1") (pin "2") (pinfunction "GND_2") (pintype "bidirectional"))
      (node (ref "U$1") (pin "24") (pinfunction "2/BOOT1_24") (pintype "bidirectional"))
      (node (ref "U$1") (pin "39") (pinfunction "AV-_39") (pintype "bidirectional"))
      (node (ref "U$2") (pin "GND") (pinfunction "GND_GND") (pintype "bidirectional"))
      (node (ref "U$3") (pin "GND") (pinfunction "GND_GND") (pintype "bidirectional"))
      (node (ref "U1") (pin "GND_1") (pinfunction "GND_1_GND_1") (pintype "power_in"))
      (node (ref "U1") (pin "GND_2") (pinfunction "GND_2_GND_2") (pintype "power_in"))
      (node (ref "U1") (pin "GND_3") (pinfunction "GND_3_GND_3") (pintype "power_in"))
      (node (ref "UART0") (pin "4") (pinfunction "4_4") (pintype "passive"))
      (node (ref "UART1") (pin "4") (pinfunction "4_4") (pintype "passive"))
      (node (ref "X1") (pin "GND@1") (pinfunction "GND4_GND@1") (pintype "power_in"))
      (node (ref "X1") (pin "GND@2") (pinfunction "GND3_GND@2") (pintype "power_in"))
      (node (ref "X1") (pin "GND@3") (pinfunction "GND2_GND@3") (pintype "power_in"))
      (node (ref "X1") (pin "GND@4") (pinfunction "GND1_GND@4") (pintype "power_in"))
      (node (ref "X2") (pin "GND@1") (pinfunction "GND4_GND@1") (pintype "power_in"))
      (node (ref "X2") (pin "GND@2") (pinfunction "GND3_GND@2") (pintype "power_in"))
      (node (ref "X2") (pin "GND@3") (pinfunction "GND2_GND@3") (pintype "power_in"))
      (node (ref "X2") (pin "GND@4") (pinfunction "GND1_GND@4") (pintype "power_in"))
      (node (ref "X3") (pin "GND@1") (pinfunction "GND4_GND@1") (pintype "power_in"))
      (node (ref "X3") (pin "GND@2") (pinfunction "GND3_GND@2") (pintype "power_in"))
      (node (ref "X3") (pin "GND@3") (pinfunction "GND2_GND@3") (pintype "power_in"))
      (node (ref "X3") (pin "GND@4") (pinfunction "GND1_GND@4") (pintype "power_in"))
      (node (ref "X31") (pin "P$6") (pinfunction "6_P$6") (pintype "passive"))
      (node (ref "X4") (pin "2") (pinfunction "K_2") (pintype "passive"))
      (node (ref "X5") (pin "GND@1") (pinfunction "GND4_GND@1") (pintype "power_in"))
      (node (ref "X5") (pin "GND@2") (pinfunction "GND3_GND@2") (pintype "power_in"))
      (node (ref "X5") (pin "GND@3") (pinfunction "GND2_GND@3") (pintype "power_in"))
      (node (ref "X5") (pin "GND@4") (pinfunction "GND1_GND@4") (pintype "power_in"))
      (node (ref "X8") (pin "GND@1") (pinfunction "GND1_GND@1") (pintype "power_in"))
      (node (ref "X8") (pin "GND@2") (pinfunction "GND2_GND@2") (pintype "power_in"))
      (node (ref "X8") (pin "GND@3") (pinfunction "GND3_GND@3") (pintype "power_in"))
      (node (ref "X8") (pin "GND@4") (pinfunction "GND4_GND@4") (pintype "power_in"))
    )
    (net (code "54") (name "IRQ-A") (class "Default")
      (node (ref "NRF24L01+") (pin "8") (pinfunction "IRQ_8") (pintype "bidirectional"))
      (node (ref "RS485") (pin "2") (pinfunction "~{RE}_2") (pintype "input"))
      (node (ref "RS485") (pin "3") (pinfunction "DE_3") (pintype "input"))
      (node (ref "U$2") (pin "D2") (pinfunction "D2_D2") (pintype "bidirectional"))
    )
    (net (code "55") (name "MOSI-A") (class "Default")
      (node (ref "NRF24L01+") (pin "6") (pinfunction "MOSI_6") (pintype "bidirectional"))
      (node (ref "U$2") (pin "D11") (pinfunction "D11_D11") (pintype "bidirectional"))
      (node (ref "X31") (pin "P$4") (pinfunction "4_P$4") (pintype "passive"))
    )
    (net (code "56") (name "Net-(C8-Pad1)") (class "Default")
      (node (ref "C8") (pin "1") (pinfunction "1_1") (pintype "passive"))
      (node (ref "R3") (pin "1") (pinfunction "1_1") (pintype "passive"))
      (node (ref "R5") (pin "1") (pinfunction "1_1") (pintype "passive"))
    )
    (net (code "57") (name "Net-(CHPD-Pad2)") (class "Default")
      (node (ref "CHPD") (pin "2") (pinfunction "2_2") (pintype "passive"))
      (node (ref "U$3") (pin "CH_PD") (pinfunction "CH_PD_CH_PD") (pintype "bidirectional"))
    )
    (net (code "58") (name "Net-(F1-2)") (class "Default")
      (node (ref "F1") (pin "P$2") (pinfunction "2_P$2") (pintype "passive"))
      (node (ref "X4") (pin "1") (pinfunction "K_1") (pintype "passive"))
    )
    (net (code "59") (name "Net-(IC31-AREF)") (class "Default")
      (node (ref "C32") (pin "1") (pinfunction "1_1") (pintype "passive"))
      (node (ref "IC31") (pin "20") (pinfunction "AREF_20") (pintype "bidirectional"))
    )
    (net (code "60") (name "Net-(IC31-PB6(XTAL1{slash}TOSC1))") (class "Default")
      (node (ref "C14") (pin "2") (pinfunction "2_2") (pintype "passive"))
      (node (ref "IC31") (pin "7") (pinfunction "PB6(XTAL1/TOSC1)_7") (pintype "bidirectional"))
      (node (ref "R4") (pin "2") (pinfunction "2_2") (pintype "passive"))
      (node (ref "Y2") (pin "P$2") (pinfunction "2_P$2") (pintype "passive"))
    )
    (net (code "61") (name "Net-(IC31-PB7(XTAL2{slash}TOSC2))") (class "Default")
      (node (ref "C15") (pin "2") (pinfunction "2_2") (pintype "passive"))
      (node (ref "IC31") (pin "8") (pinfunction "PB7(XTAL2/TOSC2)_8") (pintype "bidirectional"))
      (node (ref "R4") (pin "1") (pinfunction "1_1") (pintype "passive"))
      (node (ref "Y2") (pin "P$1") (pinfunction "1_P$1") (pintype "passive"))
    )
    (net (code "62") (name "Net-(L1-Pad1)") (class "Default")
      (node (ref "L1") (pin "1") (pinfunction "1_1") (pintype "passive"))
      (node (ref "U$2") (pin "VCC") (pinfunction "VCC_VCC") (pintype "bidirectional"))
    )
    (net (code "63") (name "Net-(NRF24L01+-VCC)") (class "Default")
      (node (ref "C5") (pin "+") (pinfunction "+_+") (pintype "passive"))
      (node (ref "C7") (pin "2") (pinfunction "2_2") (pintype "passive"))
      (node (ref "L1") (pin "2") (pinfunction "2_2") (pintype "passive"))
      (node (ref "NRF24L01+") (pin "2") (pinfunction "VCC_2") (pintype "power_in"))
    )
    (net (code "64") (name "Net-(PRG-Pad1)") (class "Default")
      (node (ref "PRG") (pin "1") (pinfunction "1_1") (pintype "passive"))
      (node (ref "U$3") (pin "GPIO0") (pinfunction "GPIO0_GPIO0") (pintype "bidirectional"))
    )
    (net (code "65") (name "Net-(U$3-RXD)") (class "Default")
      (node (ref "RX") (pin "2") (pinfunction "2_2") (pintype "passive"))
      (node (ref "U$3") (pin "RX") (pinfunction "RXD_RX") (pintype "bidirectional"))
    )
    (net (code "66") (name "Net-(U$3-TXD)") (class "Default")
      (node (ref "TX") (pin "2") (pinfunction "2_2") (pintype "passive"))
      (node (ref "U$3") (pin "TX") (pinfunction "TXD_TX") (pintype "bidirectional"))
    )
    (net (code "67") (name "Net-(X8-ANT)") (class "Default")
      (node (ref "ANT") (pin "1") (pinfunction "1_1") (pintype "passive"))
      (node (ref "U1") (pin "ANT") (pinfunction "ANT_ANT") (pintype "passive"))
      (node (ref "X8") (pin "P") (pinfunction "ANT_P") (pintype "bidirectional"))
    )
    (net (code "68") (name "R1-HM") (class "Default")
      (node (ref "HMMOD-UART") (pin "5") (pinfunction "TX_5") (pintype "bidirectional"))
      (node (ref "R1") (pin "3") (pinfunction "3_3") (pintype "passive"))
    )
    (net (code "69") (name "R1-MY") (class "Default")
      (node (ref "IC31") (pin "31") (pinfunction "PD1(TXD)_31") (pintype "bidirectional"))
      (node (ref "R1") (pin "1") (pinfunction "1_1") (pintype "passive"))
    )
    (net (code "70") (name "T1-HM") (class "Default")
      (node (ref "HMMOD-UART") (pin "6") (pinfunction "RX_6") (pintype "bidirectional"))
      (node (ref "T1") (pin "3") (pinfunction "3_3") (pintype "passive"))
    )
    (net (code "71") (name "T1-MY") (class "Default")
      (node (ref "IC31") (pin "30") (pinfunction "PD0(RXD)_30") (pintype "bidirectional"))
      (node (ref "T1") (pin "1") (pinfunction "1_1") (pintype "passive"))
    )
    (net (code "72") (name "VCC") (class "Default")
      (node (ref "3V3") (pin "1") (pinfunction "1_1") (pintype "passive"))
      (node (ref "C1") (pin "2") (pinfunction "2_2") (pintype "passive"))
      (node (ref "C11") (pin "2") (pinfunction "2_2") (pintype "passive"))
      (node (ref "C12") (pin "1") (pinfunction "1_1") (pintype "passive"))
      (node (ref "C2") (pin "2") (pinfunction "2_2") (pintype "passive"))
      (node (ref "C3") (pin "2") (pinfunction "2_2") (pintype "passive"))
      (node (ref "C31") (pin "1") (pinfunction "1_1") (pintype "passive"))
      (node (ref "C4") (pin "2") (pinfunction "2_2") (pintype "passive"))
      (node (ref "C6") (pin "1") (pinfunction "1_1") (pintype "passive"))
      (node (ref "CC0") (pin "VCC") (pinfunction "VCC_VCC") (pintype "power_in"))
      (node (ref "CC1") (pin "VCC") (pinfunction "VCC_VCC") (pintype "power_in"))
      (node (ref "CC2") (pin "VCC") (pinfunction "VCC_VCC") (pintype "power_in"))
      (node (ref "CC2-EXT") (pin "VCC@0") (pinfunction "VCC_VCC@0") (pintype "power_in"))
      (node (ref "CC2-EXT") (pin "VCC@1") (pinfunction "VCC_VCC@1") (pintype "power_in"))
      (node (ref "CC3") (pin "VCC") (pinfunction "VCC_VCC") (pintype "power_in"))
      (node (ref "CC3-EXT") (pin "VCC@0") (pinfunction "VCC_VCC@0") (pintype "power_in"))
      (node (ref "CC3-EXT") (pin "VCC@1") (pinfunction "VCC_VCC@1") (pintype "power_in"))
      (node (ref "CHPD") (pin "1") (pinfunction "1_1") (pintype "passive"))
      (node (ref "DBG") (pin "1") (pinfunction "1_1") (pintype "passive"))
      (node (ref "HMMOD-UART") (pin "1") (pinfunction "VCC_1") (pintype "power_in"))
      (node (ref "IC2") (pin "10") (pinfunction "V+_10") (pintype "power_in"))
      (node (ref "IC2") (pin "11") (pinfunction "V+_11") (pintype "power_in"))
      (node (ref "IC31") (pin "18") (pinfunction "AVCC_18") (pintype "bidirectional"))
      (node (ref "IC31") (pin "4") (pinfunction "VCC_4") (pintype "bidirectional"))
      (node (ref "IC31") (pin "6") (pinfunction "VCC_6") (pintype "bidirectional"))
      (node (ref "R2") (pin "2") (pinfunction "2_2") (pintype "passive"))
      (node (ref "R34") (pin "1") (pinfunction "1_1") (pintype "passive"))
      (node (ref "RADIO0B") (pin "VCC") (pinfunction "VCC_VCC") (pintype "power_in"))
      (node (ref "RADIO1B") (pin "VCC") (pinfunction "VCC_VCC") (pintype "power_in"))
      (node (ref "RADIO2B") (pin "VCC") (pinfunction "VCC_VCC") (pintype "power_in"))
      (node (ref "RADIO3B") (pin "VCC") (pinfunction "VCC_VCC") (pintype "power_in"))
      (node (ref "U$1") (pin "1") (pinfunction "VCC_1") (pintype "bidirectional"))
      (node (ref "U$1") (pin "40") (pinfunction "AV+_40") (pintype "bidirectional"))
      (node (ref "U$2") (pin "RAW") (pinfunction "RAW_RAW") (pintype "bidirectional"))
      (node (ref "U$3") (pin "VCC") (pinfunction "VCC_VCC") (pintype "bidirectional"))
      (node (ref "U1") (pin "3.3V") (pinfunction "3.3V_3.3V") (pintype "power_in"))
      (node (ref "UART0") (pin "1") (pinfunction "1_1") (pintype "passive"))
      (node (ref "UART1") (pin "1") (pinfunction "1_1") (pintype "passive"))
      (node (ref "X31") (pin "P$2") (pinfunction "2_P$2") (pintype "passive"))
    )
    (net (code "73") (name "unconnected-(CC3-EXT-PadGDO0)") (class "Default")
      (node (ref "CC3-EXT") (pin "GDO0") (pinfunction "GDO0_GDO0") (pintype "bidirectional"))
    )
    (net (code "74") (name "unconnected-(HMMOD-UART-C2D-Pad3)") (class "Default")
      (node (ref "HMMOD-UART") (pin "3") (pinfunction "C2D_3") (pintype "bidirectional"))
    )
    (net (code "75") (name "unconnected-(HMMOD-UART-\\~{RESET}-Pad4)") (class "Default")
      (node (ref "HMMOD-UART") (pin "4") (pinfunction "\\~{RESET}_4") (pintype "bidirectional"))
    )
    (net (code "76") (name "unconnected-(IC2-NC-Pad9)") (class "Default")
      (node (ref "IC2") (pin "9") (pinfunction "NC_9") (pintype "no_connect"))
    )
    (net (code "77") (name "unconnected-(IC31-ADC6-Pad19)") (class "Default")
      (node (ref "IC31") (pin "19") (pinfunction "ADC6_19") (pintype "bidirectional"))
    )
    (net (code "78") (name "unconnected-(IC31-ADC7-Pad22)") (class "Default")
      (node (ref "IC31") (pin "22") (pinfunction "ADC7_22") (pintype "bidirectional"))
    )
    (net (code "79") (name "unconnected-(IC31-PB0(ICP)-Pad12)") (class "Default")
      (node (ref "IC31") (pin "12") (pinfunction "PB0(ICP)_12") (pintype "bidirectional"))
    )
    (net (code "80") (name "unconnected-(IC31-PC0(ADC0)-Pad23)") (class "Default")
      (node (ref "IC31") (pin "23") (pinfunction "PC0(ADC0)_23") (pintype "bidirectional"))
    )
    (net (code "81") (name "unconnected-(IC31-PC1(ADC1)-Pad24)") (class "Default")
      (node (ref "IC31") (pin "24") (pinfunction "PC1(ADC1)_24") (pintype "bidirectional"))
    )
    (net (code "82") (name "unconnected-(IC31-PC2(ADC2)-Pad25)") (class "Default")
      (node (ref "IC31") (pin "25") (pinfunction "PC2(ADC2)_25") (pintype "bidirectional"))
    )
    (net (code "83") (name "unconnected-(IC31-PC3(ADC3)-Pad26)") (class "Default")
      (node (ref "IC31") (pin "26") (pinfunction "PC3(ADC3)_26") (pintype "bidirectional"))
    )
    (net (code "84") (name "unconnected-(IC31-PC4(ADC4{slash}SDA)-Pad27)") (class "Default")
      (node (ref "IC31") (pin "27") (pinfunction "PC4(ADC4/SDA)_27") (pintype "bidirectional"))
    )
    (net (code "85") (name "unconnected-(IC31-PC5(ADC5{slash}SCL)-Pad28)") (class "Default")
      (node (ref "IC31") (pin "28") (pinfunction "PC5(ADC5/SCL)_28") (pintype "bidirectional"))
    )
    (net (code "86") (name "unconnected-(IC31-PD3(INT1)-Pad1)") (class "Default")
      (node (ref "IC31") (pin "1") (pinfunction "PD3(INT1)_1") (pintype "bidirectional"))
    )
    (net (code "87") (name "unconnected-(IC31-PD4(XCK{slash}T0)-Pad2)") (class "Default")
      (node (ref "IC31") (pin "2") (pinfunction "PD4(XCK/T0)_2") (pintype "bidirectional"))
    )
    (net (code "88") (name "unconnected-(IC31-PD5(T1)-Pad9)") (class "Default")
      (node (ref "IC31") (pin "9") (pinfunction "PD5(T1)_9") (pintype "bidirectional"))
    )
    (net (code "89") (name "unconnected-(IC31-PD6(AIN0)-Pad10)") (class "Default")
      (node (ref "IC31") (pin "10") (pinfunction "PD6(AIN0)_10") (pintype "bidirectional"))
    )
    (net (code "90") (name "unconnected-(IC31-PD7(AIN1)-Pad11)") (class "Default")
      (node (ref "IC31") (pin "11") (pinfunction "PD7(AIN1)_11") (pintype "bidirectional"))
    )
    (net (code "91") (name "unconnected-(U$1-23{slash}USB_DP-Pad12)") (class "Default")
      (node (ref "U$1") (pin "12") (pinfunction "23/USB_DP_12") (pintype "bidirectional"))
    )
    (net (code "92") (name "unconnected-(U$1-24{slash}USB_DM-Pad13)") (class "Default")
      (node (ref "U$1") (pin "13") (pinfunction "24/USB_DM_13") (pintype "bidirectional"))
    )
    (net (code "93") (name "unconnected-(U$1-BUT-Pad3)") (class "Default")
      (node (ref "U$1") (pin "3") (pinfunction "BUT_3") (pintype "bidirectional"))
    )
    (net (code "94") (name "unconnected-(U$1-VBAT-Pad38)") (class "Default")
      (node (ref "U$1") (pin "38") (pinfunction "VBAT_38") (pintype "bidirectional"))
    )
    (net (code "95") (name "unconnected-(U$2-GND1-PadGND4)") (class "Default")
      (node (ref "U$2") (pin "GND4") (pinfunction "GND1_GND4") (pintype "bidirectional"))
    )
    (net (code "96") (name "unconnected-(U$2-GND2-PadGND1)") (class "Default")
      (node (ref "U$2") (pin "GND1") (pinfunction "GND2_GND1") (pintype "bidirectional"))
    )
    (net (code "97") (name "unconnected-(U$2-GND3-PadGND2)") (class "Default")
      (node (ref "U$2") (pin "GND2") (pinfunction "GND3_GND2") (pintype "bidirectional"))
    )
    (net (code "98") (name "unconnected-(U$2-GND4-PadGND3)") (class "Default")
      (node (ref "U$2") (pin "GND3") (pinfunction "GND4_GND3") (pintype "bidirectional"))
    )
    (net (code "99") (name "unconnected-(U$2-PadA0)") (class "Default")
      (node (ref "U$2") (pin "A0") (pinfunction "A0_A0") (pintype "bidirectional"))
    )
    (net (code "100") (name "unconnected-(U$2-PadA1)") (class "Default")
      (node (ref "U$2") (pin "A1") (pinfunction "A1_A1") (pintype "bidirectional"))
    )
    (net (code "101") (name "unconnected-(U$2-PadA2)") (class "Default")
      (node (ref "U$2") (pin "A2") (pinfunction "A2_A2") (pintype "bidirectional"))
    )
    (net (code "102") (name "unconnected-(U$2-PadA3)") (class "Default")
      (node (ref "U$2") (pin "A3") (pinfunction "A3_A3") (pintype "bidirectional"))
    )
    (net (code "103") (name "unconnected-(U$2-PadA4)") (class "Default")
      (node (ref "U$2") (pin "A4") (pinfunction "A4_A4") (pintype "bidirectional"))
    )
    (net (code "104") (name "unconnected-(U$2-PadA5)") (class "Default")
      (node (ref "U$2") (pin "A5") (pinfunction "A5_A5") (pintype "bidirectional"))
    )
    (net (code "105") (name "unconnected-(U$2-PadA6)") (class "Default")
      (node (ref "U$2") (pin "A6") (pinfunction "A6_A6") (pintype "bidirectional"))
    )
    (net (code "106") (name "unconnected-(U$2-PadA7)") (class "Default")
      (node (ref "U$2") (pin "A7") (pinfunction "A7_A7") (pintype "bidirectional"))
    )
    (net (code "107") (name "unconnected-(U$2-PadD3)") (class "Default")
      (node (ref "U$2") (pin "D3") (pinfunction "D3_D3") (pintype "bidirectional"))
    )
    (net (code "108") (name "unconnected-(U$2-PadD4)") (class "Default")
      (node (ref "U$2") (pin "D4") (pinfunction "D4_D4") (pintype "bidirectional"))
    )
    (net (code "109") (name "unconnected-(U$2-PadD5)") (class "Default")
      (node (ref "U$2") (pin "D5") (pinfunction "D5_D5") (pintype "bidirectional"))
    )
    (net (code "110") (name "unconnected-(U$2-PadD6)") (class "Default")
      (node (ref "U$2") (pin "D6") (pinfunction "D6_D6") (pintype "bidirectional"))
    )
    (net (code "111") (name "unconnected-(U$2-PadD7)") (class "Default")
      (node (ref "U$2") (pin "D7") (pinfunction "D7_D7") (pintype "bidirectional"))
    )
    (net (code "112") (name "unconnected-(U$2-PadDTR)") (class "Default")
      (node (ref "U$2") (pin "DTR") (pinfunction "DTR_DTR") (pintype "bidirectional"))
    )
    (net (code "113") (name "unconnected-(U$2-PadRST)") (class "Default")
      (node (ref "U$2") (pin "RST") (pinfunction "RST_RST") (pintype "bidirectional"))
    )
    (net (code "114") (name "unconnected-(U$2-PadRST1)") (class "Default")
      (node (ref "U$2") (pin "RST1") (pinfunction "RST1_RST1") (pintype "bidirectional"))
    )
    (net (code "115") (name "unconnected-(U$2-PadRX1-1)") (class "Default")
      (node (ref "U$2") (pin "RX1-1") (pinfunction "RX1-1_RX1-1") (pintype "bidirectional"))
    )
    (net (code "116") (name "unconnected-(U$2-PadTX0-1)") (class "Default")
      (node (ref "U$2") (pin "TX0-1") (pinfunction "TX0-1_TX0-1") (pintype "bidirectional"))
    )
    (net (code "117") (name "unconnected-(U$2-PadVCC1)") (class "Default")
      (node (ref "U$2") (pin "VCC1") (pinfunction "VCC1_VCC1") (pintype "bidirectional"))
    )
    (net (code "118") (name "unconnected-(U$3-PadGPIO2)") (class "Default")
      (node (ref "U$3") (pin "GPIO2") (pinfunction "GPIO2_GPIO2") (pintype "bidirectional"))
    )
    (net (code "119") (name "unconnected-(U$3-PadRST)") (class "Default")
      (node (ref "U$3") (pin "RST") (pinfunction "RST_RST") (pintype "bidirectional"))
    )
    (net (code "120") (name "unconnected-(U1-PadDIO1)") (class "Default")
      (node (ref "U1") (pin "DIO1") (pinfunction "DIO1_DIO1") (pintype "bidirectional"))
    )
    (net (code "121") (name "unconnected-(U1-PadDIO2)") (class "Default")
      (node (ref "U1") (pin "DIO2") (pinfunction "DIO2_DIO2") (pintype "bidirectional"))
    )
    (net (code "122") (name "unconnected-(U1-PadRESET)") (class "Default")
      (node (ref "U1") (pin "RESET") (pinfunction "RESET_RESET") (pintype "input"))
    )
  )
)
